# FC_Sheet1.net
KiCad netlist of a schematic drawn in Altium Designer
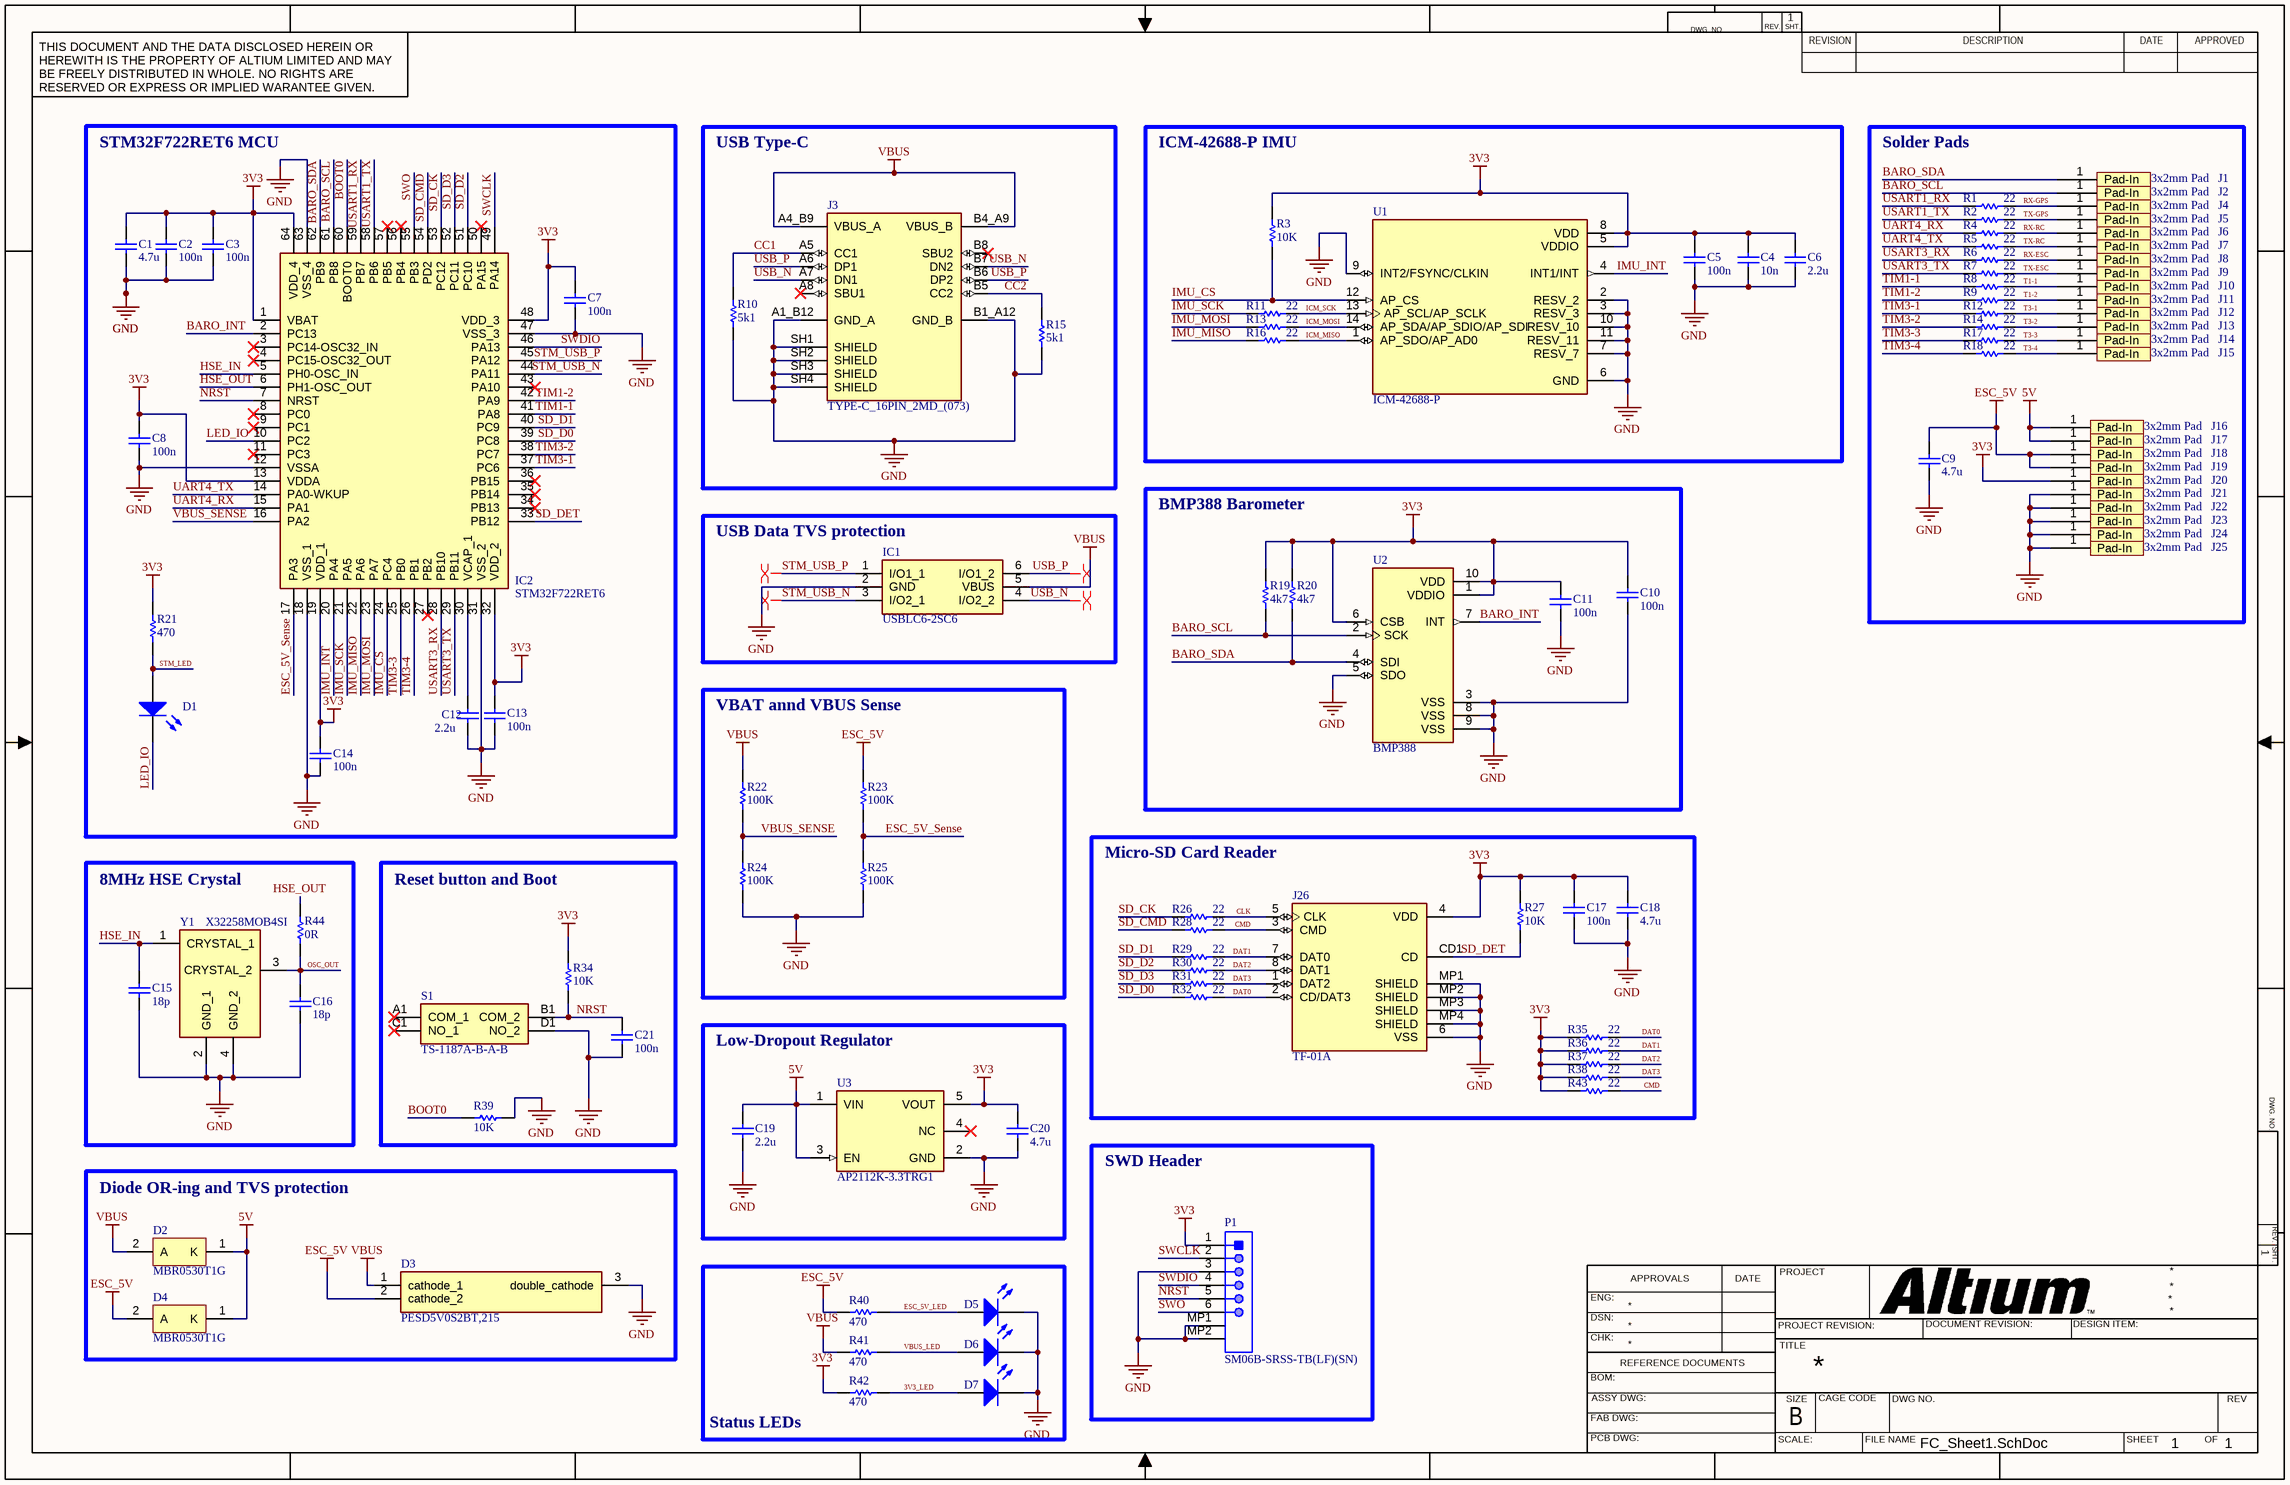
[diagram p0: FC_Sheet1.SchDoc]

(export (version "E")
  (design (tool "Eeschema 10.0.6"))
  (components
    (comp (ref "C1")
      (value "4.7u")
      (footprint "CAPC1608X90X40NL10T20")
      (description "4.7uF 0603 Capacitor")
      (libsource (lib "Simulation Generic Components") (part "Capacitor"))
    )
    (comp (ref "C2")
      (value "100n")
      (footprint "CAPC0402(1005)60_L")
      (description "100nF 0402 Capacitor")
      (libsource (lib "Simulation Generic Components") (part "Capacitor"))
    )
    (comp (ref "C3")
      (value "100n")
      (footprint "CAPC0402(1005)60_L")
      (description "100nF 0402 Capacitor")
      (libsource (lib "Simulation Generic Components") (part "Capacitor"))
    )
    (comp (ref "C4")
      (value "10n")
      (footprint "CAPC0402(1005)60_L")
      (description "10nF 0402 Capacitor")
      (libsource (lib "Simulation Generic Components") (part "Capacitor"))
    )
    (comp (ref "C5")
      (value "100n")
      (footprint "CAPC0402(1005)60_L")
      (description "100nF 0402 Capacitor")
      (libsource (lib "Simulation Generic Components") (part "Capacitor"))
    )
    (comp (ref "C6")
      (value "2.2u")
      (footprint "CAPC1608X90X40NL10T20")
      (description "2.2uF 0603 Capacitor")
      (libsource (lib "Simulation Generic Components") (part "Capacitor"))
    )
    (comp (ref "C7")
      (value "100n")
      (footprint "CAPC0402(1005)60_L")
      (description "100nF 0402 Capacitor")
      (libsource (lib "Simulation Generic Components") (part "Capacitor"))
    )
    (comp (ref "C8")
      (value "100n")
      (footprint "CAPC0402(1005)60_L")
      (description "100nF 0402 Capacitor")
      (libsource (lib "Simulation Generic Components") (part "Capacitor"))
    )
    (comp (ref "C9")
      (value "4.7u")
      (footprint "CAPC1608X90X40NL10T20")
      (description "4.7uF 0603 Capacitor")
      (libsource (lib "Simulation Generic Components") (part "Capacitor"))
    )
    (comp (ref "C10")
      (value "100n")
      (footprint "CAPC0402(1005)60_L")
      (description "100nF 0402 Capacitor")
      (libsource (lib "Simulation Generic Components") (part "Capacitor"))
    )
    (comp (ref "C11")
      (value "100n")
      (footprint "CAPC0402(1005)60_L")
      (description "100nF 0402 Capacitor")
      (libsource (lib "Simulation Generic Components") (part "Capacitor"))
    )
    (comp (ref "C12")
      (value "2.2u")
      (footprint "CAPC1608X90X40NL10T20")
      (description "2.2uF 0603 Capacitor")
      (libsource (lib "Simulation Generic Components") (part "Capacitor"))
    )
    (comp (ref "C13")
      (value "100n")
      (footprint "CAPC0402(1005)60_L")
      (description "100nF 0402 Capacitor")
      (libsource (lib "Simulation Generic Components") (part "Capacitor"))
    )
    (comp (ref "C14")
      (value "100n")
      (footprint "CAPC0402(1005)60_L")
      (description "100nF 0402 Capacitor")
      (libsource (lib "Simulation Generic Components") (part "Capacitor"))
    )
    (comp (ref "C15")
      (value "18p")
      (footprint "CAPC0402(1005)60_L")
      (description "18pF 0402 Capacitor")
      (libsource (lib "Simulation Generic Components") (part "Capacitor"))
    )
    (comp (ref "C16")
      (value "18p")
      (footprint "CAPC0402(1005)60_L")
      (description "18pF 0402 Capacitor")
      (libsource (lib "Simulation Generic Components") (part "Capacitor"))
    )
    (comp (ref "C17")
      (value "100n")
      (footprint "CAPC0402(1005)60_L")
      (description "100nF 0402 Capacitor")
      (libsource (lib "Simulation Generic Components") (part "Capacitor"))
    )
    (comp (ref "C18")
      (value "4.7u")
      (footprint "CAPC1608X90X40NL10T20")
      (description "4.7uF 0603 Capacitor")
      (libsource (lib "Simulation Generic Components") (part "Capacitor"))
    )
    (comp (ref "C19")
      (value "2.2u")
      (footprint "CAPC1608X90X40NL10T20")
      (description "2.2uF 0603 Capacitor")
      (libsource (lib "Simulation Generic Components") (part "Capacitor"))
    )
    (comp (ref "C20")
      (value "4.7u")
      (footprint "CAPC1608X90X40NL10T20")
      (description "4.7uF 0603 Capacitor")
      (libsource (lib "Simulation Generic Components") (part "Capacitor"))
    )
    (comp (ref "C21")
      (value "100n")
      (footprint "CAPC0402(1005)60_L")
      (description "100nF 0402 Capacitor")
      (libsource (lib "Simulation Generic Components") (part "Capacitor"))
    )
    (comp (ref "D1")
      (value "Red 0603 Light-Emitting Diode")
      (footprint "LTST-C191KRKT_V")
      (libsource (lib "Simulation Generic Components") (part "LED"))
    )
    (comp (ref "D2")
      (value "MBR0530T1G")
      (footprint "ONSC-SOD-123-2-425-04_V")
      (description "Schottky Power Rectifier, 2-Pin SOD-123, Pb-Free, Tape and Reel")
      (fields (field (name "MANUFACTURER") "On Semiconductor"))
      (libsource (lib "Altium Content Vault") (part "ONSC-D-K1A2-2_A"))
    )
    (comp (ref "D3")
      (value "PESD5V0S2BT,215")
      (footprint "SamacSys:SOT95P230X110-3N")
      (description "Diode")
      (fields (field (name "MOUSER PART NUMBER") "771-PESD5V0S2BT-T/R"))
      (libsource (lib "*") (part "PESD5V0S2BT,215"))
    )
    (comp (ref "D4")
      (value "MBR0530T1G")
      (footprint "ONSC-SOD-123-2-425-04_V")
      (description "Schottky Power Rectifier, 2-Pin SOD-123, Pb-Free, Tape and Reel")
      (fields (field (name "MANUFACTURER") "On Semiconductor"))
      (libsource (lib "Altium Content Vault") (part "ONSC-D-K1A2-2_A"))
    )
    (comp (ref "D5")
      (value "Red 0603 Light-Emitting Diode")
      (footprint "LTST-C191KRKT_V")
      (libsource (lib "Simulation Generic Components") (part "LED"))
    )
    (comp (ref "D6")
      (value "Red 0603 Light-Emitting Diode")
      (footprint "LTST-C191KRKT_V")
      (libsource (lib "Simulation Generic Components") (part "LED"))
    )
    (comp (ref "D7")
      (value "Red 0603 Light-Emitting Diode")
      (footprint "LTST-C191KRKT_V")
      (libsource (lib "Simulation Generic Components") (part "LED"))
    )
    (comp (ref "IC1")
      (value "USBLC6-2SC6")
      (footprint "SamacSys:SOT95P280X145-6N")
      (description "Integrated Circuit")
      (fields (field (name "MOUSER PART NUMBER") "511-USBLC6-2SC6"))
      (libsource (lib "SamacSys") (part "USBLC6-2SC6"))
    )
    (comp (ref "IC2")
      (value "STM32F722RET6")
      (footprint "SamacSys:QFP50P1200X1200X160-64N")
      (description "Integrated Circuit")
      (fields (field (name "MOUSER PART NUMBER") "511-STM32F722RET6"))
      (libsource (lib "*") (part "STM32F722RET6"))
    )
    (comp (ref "J1")
      (value "3x2mm Pad")
      (footprint "3x2mm Pad-Footprint-1")
      (description "3mm x 2mm Pad to solder")
      (libsource (lib "Barney's Workspace") (part "3x2mm Pad-Symbol-1"))
    )
    (comp (ref "J2")
      (value "3x2mm Pad")
      (footprint "3x2mm Pad-Footprint-1")
      (description "3mm x 2mm Pad to solder")
      (libsource (lib "Barney's Workspace") (part "3x2mm Pad-Symbol-1"))
    )
    (comp (ref "J3")
      (value "TYPE-C_16PIN_2MD_(073)")
      (footprint "SHOUHAN_TYPE-C_16PIN_2MD_(073)")
      (description "DC-5V 5A Type C USB")
      (fields (field (name "MP") "TYPE-C 16PIN 2MD (073)") (field (name "MF") "Shouhan"))
      (libsource (lib "Barney's Workspace") (part "TYPE-C_16PIN_2MD_(073)"))
    )
    (comp (ref "J4")
      (value "3x2mm Pad")
      (footprint "3x2mm Pad-Footprint-1")
      (description "3mm x 2mm Pad to solder")
      (libsource (lib "Barney's Workspace") (part "3x2mm Pad-Symbol-1"))
    )
    (comp (ref "J5")
      (value "3x2mm Pad")
      (footprint "3x2mm Pad-Footprint-1")
      (description "3mm x 2mm Pad to solder")
      (libsource (lib "Barney's Workspace") (part "3x2mm Pad-Symbol-1"))
    )
    (comp (ref "J6")
      (value "3x2mm Pad")
      (footprint "3x2mm Pad-Footprint-1")
      (description "3mm x 2mm Pad to solder")
      (libsource (lib "Barney's Workspace") (part "3x2mm Pad-Symbol-1"))
    )
    (comp (ref "J7")
      (value "3x2mm Pad")
      (footprint "3x2mm Pad-Footprint-1")
      (description "3mm x 2mm Pad to solder")
      (libsource (lib "Barney's Workspace") (part "3x2mm Pad-Symbol-1"))
    )
    (comp (ref "J8")
      (value "3x2mm Pad")
      (footprint "3x2mm Pad-Footprint-1")
      (description "3mm x 2mm Pad to solder")
      (libsource (lib "Barney's Workspace") (part "3x2mm Pad-Symbol-1"))
    )
    (comp (ref "J9")
      (value "3x2mm Pad")
      (footprint "3x2mm Pad-Footprint-1")
      (description "3mm x 2mm Pad to solder")
      (libsource (lib "Barney's Workspace") (part "3x2mm Pad-Symbol-1"))
    )
    (comp (ref "J10")
      (value "3x2mm Pad")
      (footprint "3x2mm Pad-Footprint-1")
      (description "3mm x 2mm Pad to solder")
      (libsource (lib "Barney's Workspace") (part "3x2mm Pad-Symbol-1"))
    )
    (comp (ref "J11")
      (value "3x2mm Pad")
      (footprint "3x2mm Pad-Footprint-1")
      (description "3mm x 2mm Pad to solder")
      (libsource (lib "Barney's Workspace") (part "3x2mm Pad-Symbol-1"))
    )
    (comp (ref "J12")
      (value "3x2mm Pad")
      (footprint "3x2mm Pad-Footprint-1")
      (description "3mm x 2mm Pad to solder")
      (libsource (lib "Barney's Workspace") (part "3x2mm Pad-Symbol-1"))
    )
    (comp (ref "J13")
      (value "3x2mm Pad")
      (footprint "3x2mm Pad-Footprint-1")
      (description "3mm x 2mm Pad to solder")
      (libsource (lib "Barney's Workspace") (part "3x2mm Pad-Symbol-1"))
    )
    (comp (ref "J14")
      (value "3x2mm Pad")
      (footprint "3x2mm Pad-Footprint-1")
      (description "3mm x 2mm Pad to solder")
      (libsource (lib "Barney's Workspace") (part "3x2mm Pad-Symbol-1"))
    )
    (comp (ref "J15")
      (value "3x2mm Pad")
      (footprint "3x2mm Pad-Footprint-1")
      (description "3mm x 2mm Pad to solder")
      (libsource (lib "Barney's Workspace") (part "3x2mm Pad-Symbol-1"))
    )
    (comp (ref "J16")
      (value "3x2mm Pad")
      (footprint "3x2mm Pad-Footprint-1")
      (description "3mm x 2mm Pad to solder")
      (libsource (lib "Barney's Workspace") (part "3x2mm Pad-Symbol-1"))
    )
    (comp (ref "J17")
      (value "3x2mm Pad")
      (footprint "3x2mm Pad-Footprint-1")
      (description "3mm x 2mm Pad to solder")
      (libsource (lib "Barney's Workspace") (part "3x2mm Pad-Symbol-1"))
    )
    (comp (ref "J18")
      (value "3x2mm Pad")
      (footprint "3x2mm Pad-Footprint-1")
      (description "3mm x 2mm Pad to solder")
      (libsource (lib "Barney's Workspace") (part "3x2mm Pad-Symbol-1"))
    )
    (comp (ref "J19")
      (value "3x2mm Pad")
      (footprint "3x2mm Pad-Footprint-1")
      (description "3mm x 2mm Pad to solder")
      (libsource (lib "Barney's Workspace") (part "3x2mm Pad-Symbol-1"))
    )
    (comp (ref "J20")
      (value "3x2mm Pad")
      (footprint "3x2mm Pad-Footprint-1")
      (description "3mm x 2mm Pad to solder")
      (libsource (lib "Barney's Workspace") (part "3x2mm Pad-Symbol-1"))
    )
    (comp (ref "J21")
      (value "3x2mm Pad")
      (footprint "3x2mm Pad-Footprint-1")
      (description "3mm x 2mm Pad to solder")
      (libsource (lib "Barney's Workspace") (part "3x2mm Pad-Symbol-1"))
    )
    (comp (ref "J22")
      (value "3x2mm Pad")
      (footprint "3x2mm Pad-Footprint-1")
      (description "3mm x 2mm Pad to solder")
      (libsource (lib "Barney's Workspace") (part "3x2mm Pad-Symbol-1"))
    )
    (comp (ref "J23")
      (value "3x2mm Pad")
      (footprint "3x2mm Pad-Footprint-1")
      (description "3mm x 2mm Pad to solder")
      (libsource (lib "Barney's Workspace") (part "3x2mm Pad-Symbol-1"))
    )
    (comp (ref "J24")
      (value "3x2mm Pad")
      (footprint "3x2mm Pad-Footprint-1")
      (description "3mm x 2mm Pad to solder")
      (libsource (lib "Barney's Workspace") (part "3x2mm Pad-Symbol-1"))
    )
    (comp (ref "J25")
      (value "3x2mm Pad")
      (footprint "3x2mm Pad-Footprint-1")
      (description "3mm x 2mm Pad to solder")
      (libsource (lib "Barney's Workspace") (part "3x2mm Pad-Symbol-1"))
    )
    (comp (ref "J26")
      (value "TF-01A")
      (footprint "TF-01A")
      (description "Standard Card Edge Connectors")
      (fields (field (name "MF") "HRO Electronics Co., Ltd."))
      (libsource (lib "Barney's Workspace") (part "TF-01A"))
    )
    (comp (ref "P1")
      (value "SM06B-SRSS-TB(LF)(SN)")
      (footprint "JST-SM06B-SRSS-TB_V")
      (description "Male Header, Pitch 1 mm, 1 x 6 Position, Height 2.95 mm, -25 to 85 degC, RoHS, Tape and Reel")
      (fields (field (name "MANUFACTURER") "JST"))
      (libsource (lib "Altium Content Vault") (part "CN-1P-2M-R6"))
    )
    (comp (ref "R1")
      (value "22")
      (footprint "RESC0402(1005)_L")
      (description "22R 0402 Resistor")
      (libsource (lib "Simulation Generic Components") (part "Resistor"))
    )
    (comp (ref "R2")
      (value "22")
      (footprint "RESC0402(1005)_L")
      (description "22R 0402 Resistor")
      (libsource (lib "Simulation Generic Components") (part "Resistor"))
    )
    (comp (ref "R3")
      (value "10K")
      (footprint "RESC0402(1005)_L")
      (description "10k 0402 Resistor")
      (libsource (lib "Simulation Generic Components") (part "Resistor"))
    )
    (comp (ref "R4")
      (value "22")
      (footprint "RESC0402(1005)_L")
      (description "22R 0402 Resistor")
      (libsource (lib "Simulation Generic Components") (part "Resistor"))
    )
    (comp (ref "R5")
      (value "22")
      (footprint "RESC0402(1005)_L")
      (description "22R 0402 Resistor")
      (libsource (lib "Simulation Generic Components") (part "Resistor"))
    )
    (comp (ref "R6")
      (value "22")
      (footprint "RESC0402(1005)_L")
      (description "22R 0402 Resistor")
      (libsource (lib "Simulation Generic Components") (part "Resistor"))
    )
    (comp (ref "R7")
      (value "22")
      (footprint "RESC0402(1005)_L")
      (description "22R 0402 Resistor")
      (libsource (lib "Simulation Generic Components") (part "Resistor"))
    )
    (comp (ref "R8")
      (value "22")
      (footprint "RESC0402(1005)_L")
      (description "22R 0402 Resistor")
      (libsource (lib "Simulation Generic Components") (part "Resistor"))
    )
    (comp (ref "R9")
      (value "22")
      (footprint "RESC0402(1005)_L")
      (description "22R 0402 Resistor")
      (libsource (lib "Simulation Generic Components") (part "Resistor"))
    )
    (comp (ref "R10")
      (value "5k1")
      (footprint "RESC0402(1005)_L")
      (description "5k1 0402 Resistor")
      (libsource (lib "Simulation Generic Components") (part "Resistor"))
    )
    (comp (ref "R11")
      (value "22")
      (footprint "RESC0402(1005)_L")
      (description "22R 0402 Resistor")
      (libsource (lib "Simulation Generic Components") (part "Resistor"))
    )
    (comp (ref "R12")
      (value "22")
      (footprint "RESC0402(1005)_L")
      (description "22R 0402 Resistor")
      (libsource (lib "Simulation Generic Components") (part "Resistor"))
    )
    (comp (ref "R13")
      (value "22")
      (footprint "RESC0402(1005)_L")
      (description "22R 0402 Resistor")
      (libsource (lib "Simulation Generic Components") (part "Resistor"))
    )
    (comp (ref "R14")
      (value "22")
      (footprint "RESC0402(1005)_L")
      (description "22R 0402 Resistor")
      (libsource (lib "Simulation Generic Components") (part "Resistor"))
    )
    (comp (ref "R15")
      (value "5k1")
      (footprint "RESC0402(1005)_L")
      (description "5k1 0402 Resistor")
      (libsource (lib "Simulation Generic Components") (part "Resistor"))
    )
    (comp (ref "R16")
      (value "22")
      (footprint "RESC0402(1005)_L")
      (description "22R 0402 Resistor")
      (libsource (lib "Simulation Generic Components") (part "Resistor"))
    )
    (comp (ref "R17")
      (value "22")
      (footprint "RESC0402(1005)_L")
      (description "22R 0402 Resistor")
      (libsource (lib "Simulation Generic Components") (part "Resistor"))
    )
    (comp (ref "R18")
      (value "22")
      (footprint "RESC0402(1005)_L")
      (description "22R 0402 Resistor")
      (libsource (lib "Simulation Generic Components") (part "Resistor"))
    )
    (comp (ref "R19")
      (value "4k7")
      (footprint "RESC0402(1005)_L")
      (description "4k7 0402 Resistor")
      (libsource (lib "Simulation Generic Components") (part "Resistor"))
    )
    (comp (ref "R20")
      (value "4k7")
      (footprint "RESC0402(1005)_L")
      (description "4k7 0402 Resistor")
      (libsource (lib "Simulation Generic Components") (part "Resistor"))
    )
    (comp (ref "R21")
      (value "470")
      (footprint "RESC1608X55X25NL10T15")
      (description "470R 0603 Resistor")
      (libsource (lib "Simulation Generic Components") (part "Resistor"))
    )
    (comp (ref "R22")
      (value "100K")
      (footprint "RESC0402(1005)_L")
      (description "100k 0402 Resistor")
      (libsource (lib "Simulation Generic Components") (part "Resistor"))
    )
    (comp (ref "R23")
      (value "100K")
      (footprint "RESC0402(1005)_L")
      (description "100k 0402 Resistor")
      (libsource (lib "Simulation Generic Components") (part "Resistor"))
    )
    (comp (ref "R24")
      (value "100K")
      (footprint "RESC0402(1005)_L")
      (description "100k 0402 Resistor")
      (libsource (lib "Simulation Generic Components") (part "Resistor"))
    )
    (comp (ref "R25")
      (value "100K")
      (footprint "RESC0402(1005)_L")
      (description "100k 0402 Resistor")
      (libsource (lib "Simulation Generic Components") (part "Resistor"))
    )
    (comp (ref "R26")
      (value "22")
      (footprint "RESC0402(1005)_L")
      (description "22R 0402 Resistor")
      (libsource (lib "Simulation Generic Components") (part "Resistor"))
    )
    (comp (ref "R27")
      (value "10K")
      (footprint "RESC0402(1005)_L")
      (description "10k 0402 Resistor")
      (libsource (lib "Simulation Generic Components") (part "Resistor"))
    )
    (comp (ref "R28")
      (value "22")
      (footprint "RESC0402(1005)_L")
      (description "22R 0402 Resistor")
      (libsource (lib "Simulation Generic Components") (part "Resistor"))
    )
    (comp (ref "R29")
      (value "22")
      (footprint "RESC0402(1005)_L")
      (description "22R 0402 Resistor")
      (libsource (lib "Simulation Generic Components") (part "Resistor"))
    )
    (comp (ref "R30")
      (value "22")
      (footprint "RESC0402(1005)_L")
      (description "22R 0402 Resistor")
      (libsource (lib "Simulation Generic Components") (part "Resistor"))
    )
    (comp (ref "R31")
      (value "22")
      (footprint "RESC0402(1005)_L")
      (description "22R 0402 Resistor")
      (libsource (lib "Simulation Generic Components") (part "Resistor"))
    )
    (comp (ref "R32")
      (value "22")
      (footprint "RESC0402(1005)_L")
      (description "22R 0402 Resistor")
      (libsource (lib "Simulation Generic Components") (part "Resistor"))
    )
    (comp (ref "R34")
      (value "10K")
      (footprint "RESC0402(1005)_L")
      (description "10k 0402 Resistor")
      (libsource (lib "Simulation Generic Components") (part "Resistor"))
    )
    (comp (ref "R35")
      (value "22")
      (footprint "RESC0402(1005)_L")
      (description "22R 0402 Resistor")
      (libsource (lib "Simulation Generic Components") (part "Resistor"))
    )
    (comp (ref "R36")
      (value "22")
      (footprint "RESC0402(1005)_L")
      (description "22R 0402 Resistor")
      (libsource (lib "Simulation Generic Components") (part "Resistor"))
    )
    (comp (ref "R37")
      (value "22")
      (footprint "RESC0402(1005)_L")
      (description "22R 0402 Resistor")
      (libsource (lib "Simulation Generic Components") (part "Resistor"))
    )
    (comp (ref "R38")
      (value "22")
      (footprint "RESC0402(1005)_L")
      (description "22R 0402 Resistor")
      (libsource (lib "Simulation Generic Components") (part "Resistor"))
    )
    (comp (ref "R39")
      (value "10K")
      (footprint "RESC0402(1005)_L")
      (description "10k 0402 Resistor")
      (libsource (lib "Simulation Generic Components") (part "Resistor"))
    )
    (comp (ref "R40")
      (value "470")
      (footprint "RESC1608X55X25NL10T15")
      (description "470R 0603 Resistor")
      (libsource (lib "Simulation Generic Components") (part "Resistor"))
    )
    (comp (ref "R41")
      (value "470")
      (footprint "RESC1608X55X25NL10T15")
      (description "470R 0603 Resistor")
      (libsource (lib "Simulation Generic Components") (part "Resistor"))
    )
    (comp (ref "R42")
      (value "470")
      (footprint "RESC1608X55X25NL10T15")
      (description "470R 0603 Resistor")
      (libsource (lib "Simulation Generic Components") (part "Resistor"))
    )
    (comp (ref "R43")
      (value "22")
      (footprint "RESC0402(1005)_L")
      (description "22R 0402 Resistor")
      (libsource (lib "Simulation Generic Components") (part "Resistor"))
    )
    (comp (ref "R44")
      (value "0R")
      (footprint "RESC0402(1005)_L")
      (description "0R 0402 Resistor")
      (libsource (lib "Simulation Generic Components") (part "Resistor"))
    )
    (comp (ref "S1")
      (value "TS-1187A-B-A-B")
      (footprint "SamacSys:TS1187ABAB")
      (description "Switch")
      (libsource (lib "*") (part "TS-1187A-B-A-B"))
    )
    (comp (ref "U1")
      (value "ICM-42688-P")
      (footprint "PQFN50P300X250X97-14N")
      (description "Accelerometer, Gyroscope, 6 Axis Sensor Output")
      (libsource (lib "Barney's Workspace") (part "ICM-42688-P"))
    )
    (comp (ref "U2")
      (value "BMP388")
      (footprint "PQFN50P200X200X80-10N")
      (description "P-Sensor SPI I2C 1, 25 Bar SMD")
      (libsource (lib "Barney's Workspace") (part "BMP388"))
    )
    (comp (ref "U3")
      (value "AP2112K-3.3TRG1")
      (footprint "FP-SOT25-IPC_A")
      (description "IC REG LINEAR 3.3V 600MA SOT25")
      (libsource (lib "Altium Content Vault") (part "c8ab751aee5229183125ab046a11caa"))
    )
    (comp (ref "Y1")
      (value "X32258MOB4SI")
      (footprint "SamacSys:X32258MOB4SI")
      (description "Crystal or Oscillator")
      (libsource (lib "SamacSys") (part "X32258MOB4SI"))
    )
  )
  (nets
    (net (code "1") (name "/3V3_LED") (class "Default")
      (node (ref "D7") (pin "1") (pinfunction "A_1") (pintype "passive"))
      (node (ref "R42") (pin "2") (pinfunction "2_2") (pintype "passive"))
    )
    (net (code "2") (name "/BARO_INT") (class "Default")
      (node (ref "IC2") (pin "2") (pinfunction "PC13_2") (pintype "passive"))
      (node (ref "U2") (pin "7") (pinfunction "INT_7") (pintype "output"))
    )
    (net (code "3") (name "/BARO_SCL") (class "Default")
      (node (ref "IC2") (pin "61") (pinfunction "PB8_61") (pintype "passive"))
      (node (ref "J2") (pin "1") (pinfunction "Pad-In_1") (pintype "passive"))
      (node (ref "R19") (pin "1") (pinfunction "1_1") (pintype "passive"))
      (node (ref "U2") (pin "2") (pinfunction "SCK_2") (pintype "input"))
    )
    (net (code "4") (name "/BARO_SDA") (class "Default")
      (node (ref "IC2") (pin "62") (pinfunction "PB9_62") (pintype "passive"))
      (node (ref "J1") (pin "1") (pinfunction "Pad-In_1") (pintype "passive"))
      (node (ref "R20") (pin "1") (pinfunction "1_1") (pintype "passive"))
      (node (ref "U2") (pin "4") (pinfunction "SDI_4") (pintype "bidirectional"))
    )
    (net (code "5") (name "/BOOT0") (class "Default")
      (node (ref "IC2") (pin "60") (pinfunction "BOOT0_60") (pintype "passive"))
      (node (ref "R39") (pin "2") (pinfunction "2_2") (pintype "passive"))
    )
    (net (code "6") (name "/CC1") (class "Default")
      (node (ref "J3") (pin "A5") (pinfunction "CC1_A5") (pintype "bidirectional"))
      (node (ref "R10") (pin "2") (pinfunction "2_2") (pintype "passive"))
    )
    (net (code "7") (name "/CC2") (class "Default")
      (node (ref "J3") (pin "B5") (pinfunction "CC2_B5") (pintype "bidirectional"))
      (node (ref "R15") (pin "2") (pinfunction "2_2") (pintype "passive"))
    )
    (net (code "8") (name "/CLK") (class "Default")
      (node (ref "J26") (pin "5") (pinfunction "CLK_5") (pintype "bidirectional"))
      (node (ref "R26") (pin "1") (pinfunction "1_1") (pintype "passive"))
    )
    (net (code "9") (name "/CMD") (class "Default")
      (node (ref "J26") (pin "3") (pinfunction "CMD_3") (pintype "bidirectional"))
      (node (ref "R28") (pin "1") (pinfunction "1_1") (pintype "passive"))
      (node (ref "R43") (pin "1") (pinfunction "1_1") (pintype "passive"))
    )
    (net (code "10") (name "/DAT0") (class "Default")
      (node (ref "J26") (pin "2") (pinfunction "CD/DAT3_2") (pintype "bidirectional"))
      (node (ref "R32") (pin "1") (pinfunction "1_1") (pintype "passive"))
      (node (ref "R35") (pin "1") (pinfunction "1_1") (pintype "passive"))
    )
    (net (code "11") (name "/DAT1") (class "Default")
      (node (ref "J26") (pin "7") (pinfunction "DAT0_7") (pintype "bidirectional"))
      (node (ref "R29") (pin "1") (pinfunction "1_1") (pintype "passive"))
      (node (ref "R36") (pin "1") (pinfunction "1_1") (pintype "passive"))
    )
    (net (code "12") (name "/DAT2") (class "Default")
      (node (ref "J26") (pin "8") (pinfunction "DAT1_8") (pintype "bidirectional"))
      (node (ref "R30") (pin "1") (pinfunction "1_1") (pintype "passive"))
      (node (ref "R37") (pin "1") (pinfunction "1_1") (pintype "passive"))
    )
    (net (code "13") (name "/DAT3") (class "Default")
      (node (ref "J26") (pin "1") (pinfunction "DAT2_1") (pintype "bidirectional"))
      (node (ref "R31") (pin "1") (pinfunction "1_1") (pintype "passive"))
      (node (ref "R38") (pin "1") (pinfunction "1_1") (pintype "passive"))
    )
    (net (code "14") (name "/ESC_5V_LED") (class "Default")
      (node (ref "D5") (pin "1") (pinfunction "A_1") (pintype "passive"))
      (node (ref "R40") (pin "2") (pinfunction "2_2") (pintype "passive"))
    )
    (net (code "15") (name "/ESC_5V_Sense") (class "Default")
      (node (ref "IC2") (pin "17") (pinfunction "PA3_17") (pintype "passive"))
      (node (ref "R23") (pin "1") (pinfunction "1_1") (pintype "passive"))
      (node (ref "R25") (pin "2") (pinfunction "2_2") (pintype "passive"))
    )
    (net (code "16") (name "/HSE_IN") (class "Default")
      (node (ref "C15") (pin "2") (pinfunction "2_2") (pintype "passive"))
      (node (ref "IC2") (pin "5") (pinfunction "PH0-OSC_IN_5") (pintype "passive"))
      (node (ref "Y1") (pin "1") (pinfunction "CRYSTAL_1_1") (pintype "passive"))
    )
    (net (code "17") (name "/HSE_OUT") (class "Default")
      (node (ref "IC2") (pin "6") (pinfunction "PH1-OSC_OUT_6") (pintype "passive"))
      (node (ref "R44") (pin "2") (pinfunction "2_2") (pintype "passive"))
    )
    (net (code "18") (name "/ICM_MISO") (class "Default")
      (node (ref "R16") (pin "1") (pinfunction "1_1") (pintype "passive"))
      (node (ref "U1") (pin "1") (pinfunction "AP_SDO/AP_AD0_1") (pintype "bidirectional"))
    )
    (net (code "19") (name "/ICM_MOSI") (class "Default")
      (node (ref "R13") (pin "1") (pinfunction "1_1") (pintype "passive"))
      (node (ref "U1") (pin "14") (pinfunction "AP_SDA/AP_SDIO/AP_SDI_14") (pintype "bidirectional"))
    )
    (net (code "20") (name "/ICM_SCK") (class "Default")
      (node (ref "R11") (pin "1") (pinfunction "1_1") (pintype "passive"))
      (node (ref "U1") (pin "13") (pinfunction "AP_SCL/AP_SCLK_13") (pintype "input"))
    )
    (net (code "21") (name "/IMU_CS") (class "Default")
      (node (ref "IC2") (pin "24") (pinfunction "PC4_24") (pintype "passive"))
      (node (ref "R3") (pin "1") (pinfunction "1_1") (pintype "passive"))
      (node (ref "U1") (pin "12") (pinfunction "AP_CS_12") (pintype "input"))
    )
    (net (code "22") (name "/IMU_INT") (class "Default")
      (node (ref "IC2") (pin "20") (pinfunction "PA4_20") (pintype "passive"))
      (node (ref "U1") (pin "4") (pinfunction "INT1/INT_4") (pintype "output"))
    )
    (net (code "23") (name "/IMU_MISO") (class "Default")
      (node (ref "IC2") (pin "22") (pinfunction "PA6_22") (pintype "passive"))
      (node (ref "R16") (pin "2") (pinfunction "2_2") (pintype "passive"))
    )
    (net (code "24") (name "/IMU_MOSI") (class "Default")
      (node (ref "IC2") (pin "23") (pinfunction "PA7_23") (pintype "passive"))
      (node (ref "R13") (pin "2") (pinfunction "2_2") (pintype "passive"))
    )
    (net (code "25") (name "/IMU_SCK") (class "Default")
      (node (ref "IC2") (pin "21") (pinfunction "PA5_21") (pintype "passive"))
      (node (ref "R11") (pin "2") (pinfunction "2_2") (pintype "passive"))
    )
    (net (code "26") (name "/LED_IO") (class "Default")
      (node (ref "D1") (pin "2") (pinfunction "K_2") (pintype "passive"))
      (node (ref "IC2") (pin "10") (pinfunction "PC2_10") (pintype "passive"))
    )
    (net (code "27") (name "/NRST") (class "Default")
      (node (ref "C21") (pin "2") (pinfunction "2_2") (pintype "passive"))
      (node (ref "IC2") (pin "7") (pinfunction "NRST_7") (pintype "passive"))
      (node (ref "P1") (pin "5") (pinfunction "5_5") (pintype "passive"))
      (node (ref "R34") (pin "1") (pinfunction "1_1") (pintype "passive"))
      (node (ref "S1") (pin "B1") (pinfunction "COM_2_B1") (pintype "passive"))
    )
    (net (code "28") (name "/OSC_OUT") (class "Default")
      (node (ref "C16") (pin "2") (pinfunction "2_2") (pintype "passive"))
      (node (ref "R44") (pin "1") (pinfunction "1_1") (pintype "passive"))
      (node (ref "Y1") (pin "3") (pinfunction "CRYSTAL_2_3") (pintype "passive"))
    )
    (net (code "29") (name "/RX-ESC") (class "Default")
      (node (ref "J8") (pin "1") (pinfunction "Pad-In_1") (pintype "passive"))
      (node (ref "R6") (pin "1") (pinfunction "1_1") (pintype "passive"))
    )
    (net (code "30") (name "/RX-GPS") (class "Default")
      (node (ref "J4") (pin "1") (pinfunction "Pad-In_1") (pintype "passive"))
      (node (ref "R1") (pin "1") (pinfunction "1_1") (pintype "passive"))
    )
    (net (code "31") (name "/RX-RC") (class "Default")
      (node (ref "J6") (pin "1") (pinfunction "Pad-In_1") (pintype "passive"))
      (node (ref "R4") (pin "1") (pinfunction "1_1") (pintype "passive"))
    )
    (net (code "32") (name "/SD_CK") (class "Default")
      (node (ref "IC2") (pin "53") (pinfunction "PC12_53") (pintype "passive"))
      (node (ref "R26") (pin "2") (pinfunction "2_2") (pintype "passive"))
    )
    (net (code "33") (name "/SD_CMD") (class "Default")
      (node (ref "IC2") (pin "54") (pinfunction "PD2_54") (pintype "passive"))
      (node (ref "R28") (pin "2") (pinfunction "2_2") (pintype "passive"))
    )
    (net (code "34") (name "/SD_D0") (class "Default")
      (node (ref "IC2") (pin "39") (pinfunction "PC8_39") (pintype "passive"))
      (node (ref "R32") (pin "2") (pinfunction "2_2") (pintype "passive"))
    )
    (net (code "35") (name "/SD_D1") (class "Default")
      (node (ref "IC2") (pin "40") (pinfunction "PC9_40") (pintype "passive"))
      (node (ref "R29") (pin "2") (pinfunction "2_2") (pintype "passive"))
    )
    (net (code "36") (name "/SD_D2") (class "Default")
      (node (ref "IC2") (pin "51") (pinfunction "PC10_51") (pintype "passive"))
      (node (ref "R30") (pin "2") (pinfunction "2_2") (pintype "passive"))
    )
    (net (code "37") (name "/SD_D3") (class "Default")
      (node (ref "IC2") (pin "52") (pinfunction "PC11_52") (pintype "passive"))
      (node (ref "R31") (pin "2") (pinfunction "2_2") (pintype "passive"))
    )
    (net (code "38") (name "/SD_DET") (class "Default")
      (node (ref "IC2") (pin "33") (pinfunction "PB12_33") (pintype "passive"))
      (node (ref "J26") (pin "CD1") (pinfunction "CD_CD1") (pintype "passive"))
      (node (ref "R27") (pin "1") (pinfunction "1_1") (pintype "passive"))
    )
    (net (code "39") (name "/STM_LED") (class "Default")
      (node (ref "D1") (pin "1") (pinfunction "A_1") (pintype "passive"))
      (node (ref "R21") (pin "2") (pinfunction "2_2") (pintype "passive"))
    )
    (net (code "40") (name "/STM_USB_N") (class "Default")
      (node (ref "IC1") (pin "3") (pinfunction "I/O2_1_3") (pintype "passive"))
      (node (ref "IC2") (pin "44") (pinfunction "PA11_44") (pintype "passive"))
    )
    (net (code "41") (name "/STM_USB_P") (class "Default")
      (node (ref "IC1") (pin "1") (pinfunction "I/O1_1_1") (pintype "passive"))
      (node (ref "IC2") (pin "45") (pinfunction "PA12_45") (pintype "passive"))
    )
    (net (code "42") (name "/SWCLK") (class "Default")
      (node (ref "IC2") (pin "49") (pinfunction "PA14_49") (pintype "passive"))
      (node (ref "P1") (pin "2") (pinfunction "2_2") (pintype "passive"))
    )
    (net (code "43") (name "/SWDIO") (class "Default")
      (node (ref "IC2") (pin "46") (pinfunction "PA13_46") (pintype "passive"))
      (node (ref "P1") (pin "4") (pinfunction "4_4") (pintype "passive"))
    )
    (net (code "44") (name "/SWO") (class "Default")
      (node (ref "IC2") (pin "55") (pinfunction "PB3_55") (pintype "passive"))
      (node (ref "P1") (pin "6") (pinfunction "6_6") (pintype "passive"))
    )
    (net (code "45") (name "/T1-1") (class "Default")
      (node (ref "J10") (pin "1") (pinfunction "Pad-In_1") (pintype "passive"))
      (node (ref "R8") (pin "1") (pinfunction "1_1") (pintype "passive"))
    )
    (net (code "46") (name "/T1-2") (class "Default")
      (node (ref "J11") (pin "1") (pinfunction "Pad-In_1") (pintype "passive"))
      (node (ref "R9") (pin "1") (pinfunction "1_1") (pintype "passive"))
    )
    (net (code "47") (name "/T3-1") (class "Default")
      (node (ref "J12") (pin "1") (pinfunction "Pad-In_1") (pintype "passive"))
      (node (ref "R12") (pin "1") (pinfunction "1_1") (pintype "passive"))
    )
    (net (code "48") (name "/T3-2") (class "Default")
      (node (ref "J13") (pin "1") (pinfunction "Pad-In_1") (pintype "passive"))
      (node (ref "R14") (pin "1") (pinfunction "1_1") (pintype "passive"))
    )
    (net (code "49") (name "/T3-3") (class "Default")
      (node (ref "J14") (pin "1") (pinfunction "Pad-In_1") (pintype "passive"))
      (node (ref "R17") (pin "1") (pinfunction "1_1") (pintype "passive"))
    )
    (net (code "50") (name "/T3-4") (class "Default")
      (node (ref "J15") (pin "1") (pinfunction "Pad-In_1") (pintype "passive"))
      (node (ref "R18") (pin "1") (pinfunction "1_1") (pintype "passive"))
    )
    (net (code "51") (name "/TIM1-1") (class "Default")
      (node (ref "IC2") (pin "41") (pinfunction "PA8_41") (pintype "passive"))
      (node (ref "R8") (pin "2") (pinfunction "2_2") (pintype "passive"))
    )
    (net (code "52") (name "/TIM1-2") (class "Default")
      (node (ref "IC2") (pin "42") (pinfunction "PA9_42") (pintype "passive"))
      (node (ref "R9") (pin "2") (pinfunction "2_2") (pintype "passive"))
    )
    (net (code "53") (name "/TIM3-1") (class "Default")
      (node (ref "IC2") (pin "37") (pinfunction "PC6_37") (pintype "passive"))
      (node (ref "R12") (pin "2") (pinfunction "2_2") (pintype "passive"))
    )
    (net (code "54") (name "/TIM3-2") (class "Default")
      (node (ref "IC2") (pin "38") (pinfunction "PC7_38") (pintype "passive"))
      (node (ref "R14") (pin "2") (pinfunction "2_2") (pintype "passive"))
    )
    (net (code "55") (name "/TIM3-3") (class "Default")
      (node (ref "IC2") (pin "25") (pinfunction "PB0_25") (pintype "passive"))
      (node (ref "R17") (pin "2") (pinfunction "2_2") (pintype "passive"))
    )
    (net (code "56") (name "/TIM3-4") (class "Default")
      (node (ref "IC2") (pin "26") (pinfunction "PB1_26") (pintype "passive"))
      (node (ref "R18") (pin "2") (pinfunction "2_2") (pintype "passive"))
    )
    (net (code "57") (name "/TX-ESC") (class "Default")
      (node (ref "J9") (pin "1") (pinfunction "Pad-In_1") (pintype "passive"))
      (node (ref "R7") (pin "1") (pinfunction "1_1") (pintype "passive"))
    )
    (net (code "58") (name "/TX-GPS") (class "Default")
      (node (ref "J5") (pin "1") (pinfunction "Pad-In_1") (pintype "passive"))
      (node (ref "R2") (pin "1") (pinfunction "1_1") (pintype "passive"))
    )
    (net (code "59") (name "/TX-RC") (class "Default")
      (node (ref "J7") (pin "1") (pinfunction "Pad-In_1") (pintype "passive"))
      (node (ref "R5") (pin "1") (pinfunction "1_1") (pintype "passive"))
    )
    (net (code "60") (name "/UART4_RX") (class "Default")
      (node (ref "IC2") (pin "15") (pinfunction "PA1_15") (pintype "passive"))
      (node (ref "R4") (pin "2") (pinfunction "2_2") (pintype "passive"))
    )
    (net (code "61") (name "/UART4_TX") (class "Default")
      (node (ref "IC2") (pin "14") (pinfunction "PA0-WKUP_14") (pintype "passive"))
      (node (ref "R5") (pin "2") (pinfunction "2_2") (pintype "passive"))
    )
    (net (code "62") (name "/USART1_RX") (class "Default")
      (node (ref "IC2") (pin "59") (pinfunction "PB7_59") (pintype "passive"))
      (node (ref "R1") (pin "2") (pinfunction "2_2") (pintype "passive"))
    )
    (net (code "63") (name "/USART1_TX") (class "Default")
      (node (ref "IC2") (pin "58") (pinfunction "PB6_58") (pintype "passive"))
      (node (ref "R2") (pin "2") (pinfunction "2_2") (pintype "passive"))
    )
    (net (code "64") (name "/USART3_RX") (class "Default")
      (node (ref "IC2") (pin "28") (pinfunction "PB10_28") (pintype "passive"))
      (node (ref "R6") (pin "2") (pinfunction "2_2") (pintype "passive"))
    )
    (net (code "65") (name "/USART3_TX") (class "Default")
      (node (ref "IC2") (pin "29") (pinfunction "PB11_29") (pintype "passive"))
      (node (ref "R7") (pin "2") (pinfunction "2_2") (pintype "passive"))
    )
    (net (code "66") (name "/USB_N") (class "Default")
      (node (ref "IC1") (pin "4") (pinfunction "I/O2_2_4") (pintype "passive"))
      (node (ref "J3") (pin "A7") (pinfunction "DN1_A7") (pintype "bidirectional"))
      (node (ref "J3") (pin "B7") (pinfunction "DN2_B7") (pintype "bidirectional"))
    )
    (net (code "67") (name "/USB_P") (class "Default")
      (node (ref "IC1") (pin "6") (pinfunction "I/O1_2_6") (pintype "passive"))
      (node (ref "J3") (pin "A6") (pinfunction "DP1_A6") (pintype "bidirectional"))
      (node (ref "J3") (pin "B6") (pinfunction "DP2_B6") (pintype "bidirectional"))
    )
    (net (code "68") (name "/VBUS_LED") (class "Default")
      (node (ref "D6") (pin "1") (pinfunction "A_1") (pintype "passive"))
      (node (ref "R41") (pin "2") (pinfunction "2_2") (pintype "passive"))
    )
    (net (code "69") (name "/VBUS_SENSE") (class "Default")
      (node (ref "IC2") (pin "16") (pinfunction "PA2_16") (pintype "passive"))
      (node (ref "R22") (pin "1") (pinfunction "1_1") (pintype "passive"))
      (node (ref "R24") (pin "2") (pinfunction "2_2") (pintype "passive"))
    )
    (net (code "70") (name "3V3") (class "Default")
      (node (ref "C1") (pin "2") (pinfunction "2_2") (pintype "passive"))
      (node (ref "C10") (pin "2") (pinfunction "2_2") (pintype "passive"))
      (node (ref "C11") (pin "2") (pinfunction "2_2") (pintype "passive"))
      (node (ref "C13") (pin "2") (pinfunction "2_2") (pintype "passive"))
      (node (ref "C14") (pin "2") (pinfunction "2_2") (pintype "passive"))
      (node (ref "C17") (pin "2") (pinfunction "2_2") (pintype "passive"))
      (node (ref "C18") (pin "2") (pinfunction "2_2") (pintype "passive"))
      (node (ref "C2") (pin "2") (pinfunction "2_2") (pintype "passive"))
      (node (ref "C20") (pin "2") (pinfunction "2_2") (pintype "passive"))
      (node (ref "C3") (pin "2") (pinfunction "2_2") (pintype "passive"))
      (node (ref "C4") (pin "2") (pinfunction "2_2") (pintype "passive"))
      (node (ref "C5") (pin "2") (pinfunction "2_2") (pintype "passive"))
      (node (ref "C6") (pin "2") (pinfunction "2_2") (pintype "passive"))
      (node (ref "C7") (pin "2") (pinfunction "2_2") (pintype "passive"))
      (node (ref "C8") (pin "2") (pinfunction "2_2") (pintype "passive"))
      (node (ref "IC2") (pin "1") (pinfunction "VBAT_1") (pintype "passive"))
      (node (ref "IC2") (pin "13") (pinfunction "VDDA_13") (pintype "passive"))
      (node (ref "IC2") (pin "19") (pinfunction "VDD_1_19") (pintype "passive"))
      (node (ref "IC2") (pin "32") (pinfunction "VDD_2_32") (pintype "passive"))
      (node (ref "IC2") (pin "48") (pinfunction "VDD_3_48") (pintype "passive"))
      (node (ref "IC2") (pin "64") (pinfunction "VDD_4_64") (pintype "passive"))
      (node (ref "J20") (pin "1") (pinfunction "Pad-In_1") (pintype "passive"))
      (node (ref "J26") (pin "4") (pinfunction "VDD_4") (pintype "power_in"))
      (node (ref "P1") (pin "1") (pinfunction "1_1") (pintype "passive"))
      (node (ref "R19") (pin "2") (pinfunction "2_2") (pintype "passive"))
      (node (ref "R20") (pin "2") (pinfunction "2_2") (pintype "passive"))
      (node (ref "R21") (pin "1") (pinfunction "1_1") (pintype "passive"))
      (node (ref "R27") (pin "2") (pinfunction "2_2") (pintype "passive"))
      (node (ref "R3") (pin "2") (pinfunction "2_2") (pintype "passive"))
      (node (ref "R34") (pin "2") (pinfunction "2_2") (pintype "passive"))
      (node (ref "R35") (pin "2") (pinfunction "2_2") (pintype "passive"))
      (node (ref "R36") (pin "2") (pinfunction "2_2") (pintype "passive"))
      (node (ref "R37") (pin "2") (pinfunction "2_2") (pintype "passive"))
      (node (ref "R38") (pin "2") (pinfunction "2_2") (pintype "passive"))
      (node (ref "R42") (pin "1") (pinfunction "1_1") (pintype "passive"))
      (node (ref "R43") (pin "2") (pinfunction "2_2") (pintype "passive"))
      (node (ref "U1") (pin "5") (pinfunction "VDDIO_5") (pintype "power_in"))
      (node (ref "U1") (pin "8") (pinfunction "VDD_8") (pintype "power_in"))
      (node (ref "U2") (pin "1") (pinfunction "VDDIO_1") (pintype "power_in"))
      (node (ref "U2") (pin "10") (pinfunction "VDD_10") (pintype "power_in"))
      (node (ref "U2") (pin "6") (pinfunction "CSB_6") (pintype "input"))
      (node (ref "U3") (pin "5") (pinfunction "VOUT_5") (pintype "power_in"))
    )
    (net (code "71") (name "5V") (class "Default")
      (node (ref "C19") (pin "2") (pinfunction "2_2") (pintype "passive"))
      (node (ref "D2") (pin "1") (pinfunction "K_1") (pintype "passive"))
      (node (ref "D4") (pin "1") (pinfunction "K_1") (pintype "passive"))
      (node (ref "J16") (pin "1") (pinfunction "Pad-In_1") (pintype "passive"))
      (node (ref "J17") (pin "1") (pinfunction "Pad-In_1") (pintype "passive"))
      (node (ref "U3") (pin "1") (pinfunction "VIN_1") (pintype "power_in"))
      (node (ref "U3") (pin "3") (pinfunction "EN_3") (pintype "input"))
    )
    (net (code "72") (name "ESC_5V") (class "Default")
      (node (ref "C9") (pin "2") (pinfunction "2_2") (pintype "passive"))
      (node (ref "D3") (pin "2") (pinfunction "cathode_2_2") (pintype "passive"))
      (node (ref "D4") (pin "2") (pinfunction "A_2") (pintype "passive"))
      (node (ref "J18") (pin "1") (pinfunction "Pad-In_1") (pintype "passive"))
      (node (ref "J19") (pin "1") (pinfunction "Pad-In_1") (pintype "passive"))
      (node (ref "R23") (pin "2") (pinfunction "2_2") (pintype "passive"))
      (node (ref "R40") (pin "1") (pinfunction "1_1") (pintype "passive"))
    )
    (net (code "73") (name "GND") (class "Default")
      (node (ref "C1") (pin "1") (pinfunction "1_1") (pintype "passive"))
      (node (ref "C10") (pin "1") (pinfunction "1_1") (pintype "passive"))
      (node (ref "C11") (pin "1") (pinfunction "1_1") (pintype "passive"))
      (node (ref "C12") (pin "1") (pinfunction "1_1") (pintype "passive"))
      (node (ref "C13") (pin "1") (pinfunction "1_1") (pintype "passive"))
      (node (ref "C14") (pin "1") (pinfunction "1_1") (pintype "passive"))
      (node (ref "C15") (pin "1") (pinfunction "1_1") (pintype "passive"))
      (node (ref "C16") (pin "1") (pinfunction "1_1") (pintype "passive"))
      (node (ref "C17") (pin "1") (pinfunction "1_1") (pintype "passive"))
      (node (ref "C18") (pin "1") (pinfunction "1_1") (pintype "passive"))
      (node (ref "C19") (pin "1") (pinfunction "1_1") (pintype "passive"))
      (node (ref "C2") (pin "1") (pinfunction "1_1") (pintype "passive"))
      (node (ref "C20") (pin "1") (pinfunction "1_1") (pintype "passive"))
      (node (ref "C21") (pin "1") (pinfunction "1_1") (pintype "passive"))
      (node (ref "C3") (pin "1") (pinfunction "1_1") (pintype "passive"))
      (node (ref "C4") (pin "1") (pinfunction "1_1") (pintype "passive"))
      (node (ref "C5") (pin "1") (pinfunction "1_1") (pintype "passive"))
      (node (ref "C6") (pin "1") (pinfunction "1_1") (pintype "passive"))
      (node (ref "C7") (pin "1") (pinfunction "1_1") (pintype "passive"))
      (node (ref "C8") (pin "1") (pinfunction "1_1") (pintype "passive"))
      (node (ref "C9") (pin "1") (pinfunction "1_1") (pintype "passive"))
      (node (ref "D3") (pin "3") (pinfunction "double_cathode_3") (pintype "passive"))
      (node (ref "D5") (pin "2") (pinfunction "K_2") (pintype "passive"))
      (node (ref "D6") (pin "2") (pinfunction "K_2") (pintype "passive"))
      (node (ref "D7") (pin "2") (pinfunction "K_2") (pintype "passive"))
      (node (ref "IC1") (pin "2") (pinfunction "GND_2") (pintype "passive"))
      (node (ref "IC2") (pin "12") (pinfunction "VSSA_12") (pintype "passive"))
      (node (ref "IC2") (pin "18") (pinfunction "VSS_1_18") (pintype "passive"))
      (node (ref "IC2") (pin "31") (pinfunction "VSS_2_31") (pintype "passive"))
      (node (ref "IC2") (pin "47") (pinfunction "VSS_3_47") (pintype "passive"))
      (node (ref "IC2") (pin "63") (pinfunction "VSS_4_63") (pintype "passive"))
      (node (ref "J21") (pin "1") (pinfunction "Pad-In_1") (pintype "passive"))
      (node (ref "J22") (pin "1") (pinfunction "Pad-In_1") (pintype "passive"))
      (node (ref "J23") (pin "1") (pinfunction "Pad-In_1") (pintype "passive"))
      (node (ref "J24") (pin "1") (pinfunction "Pad-In_1") (pintype "passive"))
      (node (ref "J25") (pin "1") (pinfunction "Pad-In_1") (pintype "passive"))
      (node (ref "J26") (pin "6") (pinfunction "VSS_6") (pintype "power_in"))
      (node (ref "J26") (pin "MP1") (pinfunction "SHIELD_MP1") (pintype "power_in"))
      (node (ref "J26") (pin "MP2") (pinfunction "SHIELD_MP2") (pintype "power_in"))
      (node (ref "J26") (pin "MP3") (pinfunction "SHIELD_MP3") (pintype "power_in"))
      (node (ref "J26") (pin "MP4") (pinfunction "SHIELD_MP4") (pintype "power_in"))
      (node (ref "J3") (pin "A1_B12") (pinfunction "GND_A_A1_B12") (pintype "power_in"))
      (node (ref "J3") (pin "B1_A12") (pinfunction "GND_B_B1_A12") (pintype "power_in"))
      (node (ref "J3") (pin "SH1") (pinfunction "SHIELD_SH1") (pintype "passive"))
      (node (ref "J3") (pin "SH2") (pinfunction "SHIELD_SH2") (pintype "passive"))
      (node (ref "J3") (pin "SH3") (pinfunction "SHIELD_SH3") (pintype "passive"))
      (node (ref "J3") (pin "SH4") (pinfunction "SHIELD_SH4") (pintype "passive"))
      (node (ref "P1") (pin "3") (pinfunction "3_3") (pintype "passive"))
      (node (ref "P1") (pin "MP1") (pinfunction "MP1_MP1") (pintype "passive"))
      (node (ref "P1") (pin "MP2") (pinfunction "MP2_MP2") (pintype "passive"))
      (node (ref "R10") (pin "1") (pinfunction "1_1") (pintype "passive"))
      (node (ref "R15") (pin "1") (pinfunction "1_1") (pintype "passive"))
      (node (ref "R24") (pin "1") (pinfunction "1_1") (pintype "passive"))
      (node (ref "R25") (pin "1") (pinfunction "1_1") (pintype "passive"))
      (node (ref "R39") (pin "1") (pinfunction "1_1") (pintype "passive"))
      (node (ref "S1") (pin "D1") (pinfunction "NO_2_D1") (pintype "passive"))
      (node (ref "U1") (pin "10") (pinfunction "RESV_10_10") (pintype "passive"))
      (node (ref "U1") (pin "11") (pinfunction "RESV_11_11") (pintype "passive"))
      (node (ref "U1") (pin "2") (pinfunction "RESV_2_2") (pintype "passive"))
      (node (ref "U1") (pin "3") (pinfunction "RESV_3_3") (pintype "passive"))
      (node (ref "U1") (pin "6") (pinfunction "GND_6") (pintype "power_in"))
      (node (ref "U1") (pin "7") (pinfunction "RESV_7_7") (pintype "passive"))
      (node (ref "U1") (pin "9") (pinfunction "INT2/FSYNC/CLKIN_9") (pintype "bidirectional"))
      (node (ref "U2") (pin "3") (pinfunction "VSS_3") (pintype "power_in"))
      (node (ref "U2") (pin "5") (pinfunction "SDO_5") (pintype "bidirectional"))
      (node (ref "U2") (pin "8") (pinfunction "VSS_8") (pintype "power_in"))
      (node (ref "U2") (pin "9") (pinfunction "VSS_9") (pintype "power_in"))
      (node (ref "U3") (pin "2") (pinfunction "GND_2") (pintype "power_in"))
      (node (ref "Y1") (pin "2") (pinfunction "GND_1_2") (pintype "passive"))
      (node (ref "Y1") (pin "4") (pinfunction "GND_2_4") (pintype "passive"))
    )
    (net (code "74") (name "Net-(IC2-VCAP_1)") (class "Default")
      (node (ref "C12") (pin "2") (pinfunction "2_2") (pintype "passive"))
      (node (ref "IC2") (pin "30") (pinfunction "VCAP_1_30") (pintype "passive"))
    )
    (net (code "75") (name "VBUS") (class "Default")
      (node (ref "D2") (pin "2") (pinfunction "A_2") (pintype "passive"))
      (node (ref "D3") (pin "1") (pinfunction "cathode_1_1") (pintype "passive"))
      (node (ref "IC1") (pin "5") (pinfunction "VBUS_5") (pintype "passive"))
      (node (ref "J3") (pin "A4_B9") (pinfunction "VBUS_A_A4_B9") (pintype "power_in"))
      (node (ref "J3") (pin "B4_A9") (pinfunction "VBUS_B_B4_A9") (pintype "power_in"))
      (node (ref "R22") (pin "2") (pinfunction "2_2") (pintype "passive"))
      (node (ref "R41") (pin "1") (pinfunction "1_1") (pintype "passive"))
    )
    (net (code "76") (name "unconnected-(IC2-PA10-Pad43)") (class "Default")
      (node (ref "IC2") (pin "43") (pinfunction "PA10_43") (pintype "passive+no_connect"))
    )
    (net (code "77") (name "unconnected-(IC2-PA15-Pad50)") (class "Default")
      (node (ref "IC2") (pin "50") (pinfunction "PA15_50") (pintype "passive+no_connect"))
    )
    (net (code "78") (name "unconnected-(IC2-PB2-Pad27)") (class "Default")
      (node (ref "IC2") (pin "27") (pinfunction "PB2_27") (pintype "passive+no_connect"))
    )
    (net (code "79") (name "unconnected-(IC2-PB4-Pad56)") (class "Default")
      (node (ref "IC2") (pin "56") (pinfunction "PB4_56") (pintype "passive+no_connect"))
    )
    (net (code "80") (name "unconnected-(IC2-PB5-Pad57)") (class "Default")
      (node (ref "IC2") (pin "57") (pinfunction "PB5_57") (pintype "passive+no_connect"))
    )
    (net (code "81") (name "unconnected-(IC2-PB13-Pad34)") (class "Default")
      (node (ref "IC2") (pin "34") (pinfunction "PB13_34") (pintype "passive+no_connect"))
    )
    (net (code "82") (name "unconnected-(IC2-PB14-Pad35)") (class "Default")
      (node (ref "IC2") (pin "35") (pinfunction "PB14_35") (pintype "passive+no_connect"))
    )
    (net (code "83") (name "unconnected-(IC2-PB15-Pad36)") (class "Default")
      (node (ref "IC2") (pin "36") (pinfunction "PB15_36") (pintype "passive+no_connect"))
    )
    (net (code "84") (name "unconnected-(IC2-PC0-Pad8)") (class "Default")
      (node (ref "IC2") (pin "8") (pinfunction "PC0_8") (pintype "passive+no_connect"))
    )
    (net (code "85") (name "unconnected-(IC2-PC1-Pad9)") (class "Default")
      (node (ref "IC2") (pin "9") (pinfunction "PC1_9") (pintype "passive+no_connect"))
    )
    (net (code "86") (name "unconnected-(IC2-PC3-Pad11)") (class "Default")
      (node (ref "IC2") (pin "11") (pinfunction "PC3_11") (pintype "passive+no_connect"))
    )
    (net (code "87") (name "unconnected-(IC2-PC14-OSC32_IN-Pad3)") (class "Default")
      (node (ref "IC2") (pin "3") (pinfunction "PC14-OSC32_IN_3") (pintype "passive+no_connect"))
    )
    (net (code "88") (name "unconnected-(IC2-PC15-OSC32_OUT-Pad4)") (class "Default")
      (node (ref "IC2") (pin "4") (pinfunction "PC15-OSC32_OUT_4") (pintype "passive+no_connect"))
    )
    (net (code "89") (name "unconnected-(J3-SBU1-PadA8)") (class "Default")
      (node (ref "J3") (pin "A8") (pinfunction "SBU1_A8") (pintype "bidirectional+no_connect"))
    )
    (net (code "90") (name "unconnected-(J3-SBU2-PadB8)") (class "Default")
      (node (ref "J3") (pin "B8") (pinfunction "SBU2_B8") (pintype "bidirectional+no_connect"))
    )
    (net (code "91") (name "unconnected-(S1-COM_1-PadA1)") (class "Default")
      (node (ref "S1") (pin "A1") (pinfunction "COM_1_A1") (pintype "passive+no_connect"))
    )
    (net (code "92") (name "unconnected-(S1-NO_1-PadC1)") (class "Default")
      (node (ref "S1") (pin "C1") (pinfunction "NO_1_C1") (pintype "passive+no_connect"))
    )
    (net (code "93") (name "unconnected-(U3-NC-Pad4)") (class "Default")
      (node (ref "U3") (pin "4") (pinfunction "NC_4") (pintype "passive+no_connect"))
    )
  )
)
